# BalanceTest.net
KiCad netlist of a schematic drawn in EAGLE
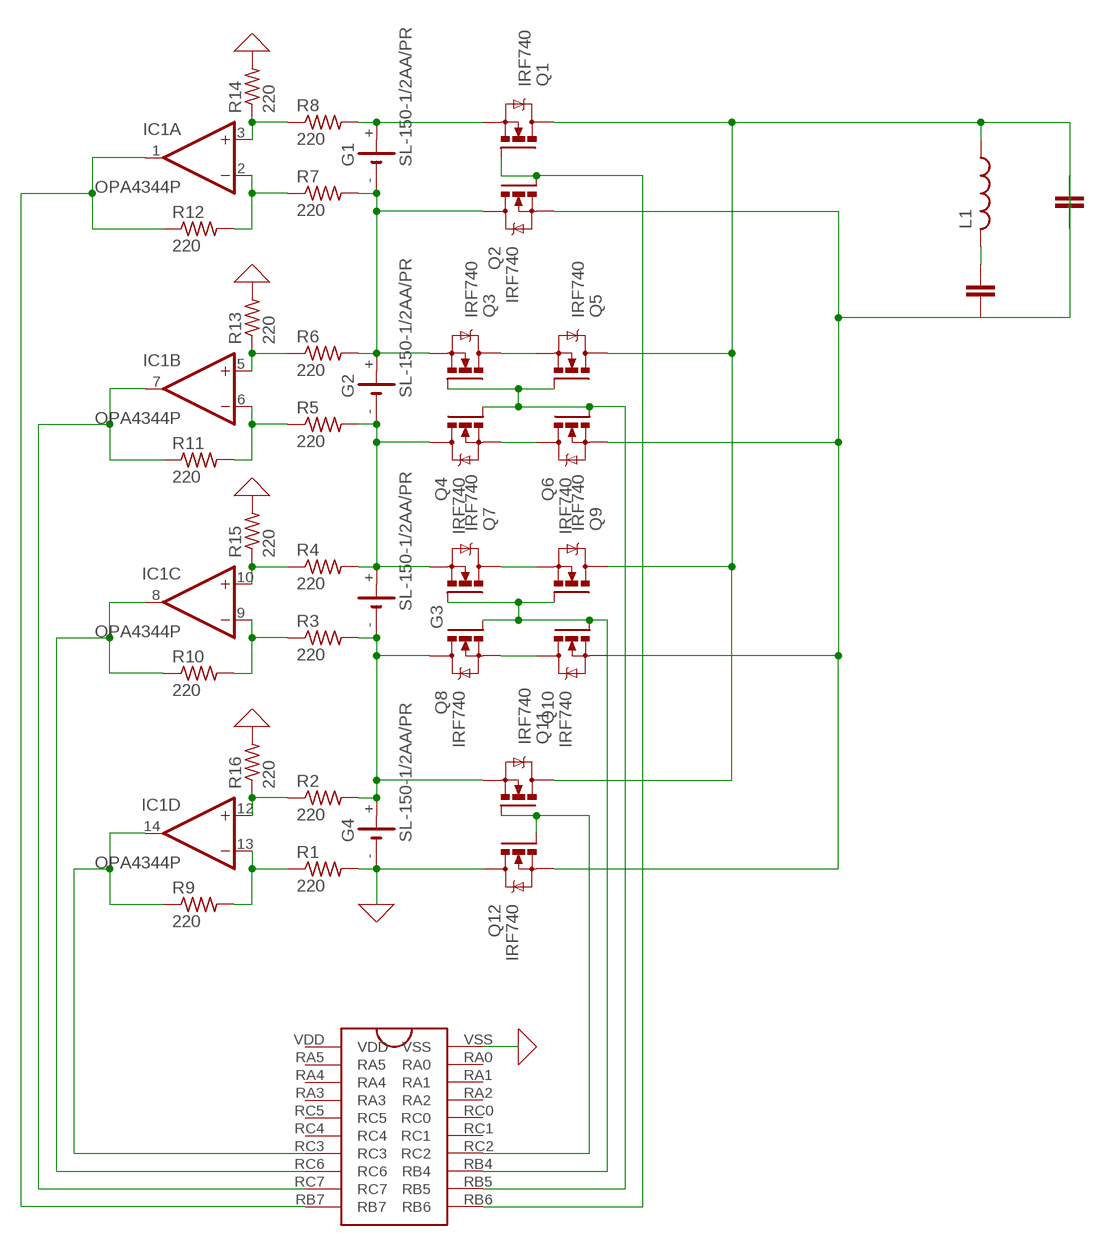
[diagram p0: schematic, sheet 1]

(export (version "E")
  (design (tool "Eeschema 10.0.6"))
  (components
    (comp (ref "G1")
      (value "SL-150-1/2AA/PR")
      (footprint "eagle-import:SL-150-1_2AA_PR")
      (libsource (lib "eagle-import") (part "SL-150-1/2AA/PR"))
    )
    (comp (ref "G2")
      (value "SL-150-1/2AA/PR")
      (footprint "eagle-import:SL-150-1_2AA_PR")
      (libsource (lib "eagle-import") (part "SL-150-1/2AA/PR"))
    )
    (comp (ref "G3")
      (value "SL-150-1/2AA/PR")
      (footprint "eagle-import:SL-150-1_2AA_PR")
      (libsource (lib "eagle-import") (part "SL-150-1/2AA/PR"))
    )
    (comp (ref "G4")
      (value "SL-150-1/2AA/PR")
      (footprint "eagle-import:SL-150-1_2AA_PR")
      (libsource (lib "eagle-import") (part "SL-150-1/2AA/PR"))
    )
    (comp (ref "IC1")
      (value "OPA4344P")
      (footprint "eagle-import:DIL14")
      (libsource (lib "eagle-import") (part "OPA4P344"))
    )
    (comp (ref "L1")
      (value "L-USIR-4")
      (footprint "eagle-import:IR-4")
      (libsource (lib "eagle-import") (part "L-USIR-4"))
    )
    (comp (ref "Q1")
      (value "IRF740")
      (footprint "eagle-import:TO220BV")
      (libsource (lib "eagle-import") (part "IRF740"))
    )
    (comp (ref "Q2")
      (value "IRF740")
      (footprint "eagle-import:TO220BV")
      (libsource (lib "eagle-import") (part "IRF740"))
    )
    (comp (ref "Q3")
      (value "IRF740")
      (footprint "eagle-import:TO220BV")
      (libsource (lib "eagle-import") (part "IRF740"))
    )
    (comp (ref "Q4")
      (value "IRF740")
      (footprint "eagle-import:TO220BV")
      (libsource (lib "eagle-import") (part "IRF740"))
    )
    (comp (ref "Q5")
      (value "IRF740")
      (footprint "eagle-import:TO220BV")
      (libsource (lib "eagle-import") (part "IRF740"))
    )
    (comp (ref "Q6")
      (value "IRF740")
      (footprint "eagle-import:TO220BV")
      (libsource (lib "eagle-import") (part "IRF740"))
    )
    (comp (ref "Q7")
      (value "IRF740")
      (footprint "eagle-import:TO220BV")
      (libsource (lib "eagle-import") (part "IRF740"))
    )
    (comp (ref "Q8")
      (value "IRF740")
      (footprint "eagle-import:TO220BV")
      (libsource (lib "eagle-import") (part "IRF740"))
    )
    (comp (ref "Q9")
      (value "IRF740")
      (footprint "eagle-import:TO220BV")
      (libsource (lib "eagle-import") (part "IRF740"))
    )
    (comp (ref "Q10")
      (value "IRF740")
      (footprint "eagle-import:TO220BV")
      (libsource (lib "eagle-import") (part "IRF740"))
    )
    (comp (ref "Q11")
      (value "IRF740")
      (footprint "eagle-import:TO220BV")
      (libsource (lib "eagle-import") (part "IRF740"))
    )
    (comp (ref "Q12")
      (value "IRF740")
      (footprint "eagle-import:TO220BV")
      (libsource (lib "eagle-import") (part "IRF740"))
    )
    (comp (ref "R1")
      (value "220")
      (footprint "eagle-import:0411_15")
      (libsource (lib "eagle-import") (part "R-US_0411/15"))
    )
    (comp (ref "R2")
      (value "220")
      (footprint "eagle-import:0411_15")
      (libsource (lib "eagle-import") (part "R-US_0411/15"))
    )
    (comp (ref "R3")
      (value "220")
      (footprint "eagle-import:0411_15")
      (libsource (lib "eagle-import") (part "R-US_0411/15"))
    )
    (comp (ref "R4")
      (value "220")
      (footprint "eagle-import:0411_15")
      (libsource (lib "eagle-import") (part "R-US_0411/15"))
    )
    (comp (ref "R5")
      (value "220")
      (footprint "eagle-import:0411_15")
      (libsource (lib "eagle-import") (part "R-US_0411/15"))
    )
    (comp (ref "R6")
      (value "220")
      (footprint "eagle-import:0411_15")
      (libsource (lib "eagle-import") (part "R-US_0411/15"))
    )
    (comp (ref "R7")
      (value "220")
      (footprint "eagle-import:0411_15")
      (libsource (lib "eagle-import") (part "R-US_0411/15"))
    )
    (comp (ref "R8")
      (value "220")
      (footprint "eagle-import:0411_15")
      (libsource (lib "eagle-import") (part "R-US_0411/15"))
    )
    (comp (ref "R9")
      (value "220")
      (footprint "eagle-import:0411_15")
      (libsource (lib "eagle-import") (part "R-US_0411/15"))
    )
    (comp (ref "R10")
      (value "220")
      (footprint "eagle-import:0411_15")
      (libsource (lib "eagle-import") (part "R-US_0411/15"))
    )
    (comp (ref "R11")
      (value "220")
      (footprint "eagle-import:0411_15")
      (libsource (lib "eagle-import") (part "R-US_0411/15"))
    )
    (comp (ref "R12")
      (value "220")
      (footprint "eagle-import:0411_15")
      (libsource (lib "eagle-import") (part "R-US_0411/15"))
    )
    (comp (ref "R13")
      (value "220")
      (footprint "eagle-import:0411_15")
      (libsource (lib "eagle-import") (part "R-US_0411/15"))
    )
    (comp (ref "R14")
      (value "220")
      (footprint "eagle-import:0411_15")
      (libsource (lib "eagle-import") (part "R-US_0411/15"))
    )
    (comp (ref "R15")
      (value "220")
      (footprint "eagle-import:0411_15")
      (libsource (lib "eagle-import") (part "R-US_0411/15"))
    )
    (comp (ref "R16")
      (value "220")
      (footprint "eagle-import:0411_15")
      (libsource (lib "eagle-import") (part "R-US_0411/15"))
    )
    (comp (ref "U1")
      (value "PIC18F15Q40SOIC")
      (footprint "eagle-import:SOIC")
      (libsource (lib "eagle-import") (part "PIC18F15Q40SOIC"))
    )
  )
  (nets
    (net (code "1") (name "GND") (class "Default")
      (node (ref "G4") (pin "-") (pinfunction "-_-") (pintype "passive"))
      (node (ref "Q12") (pin "D") (pinfunction "D_D") (pintype "passive"))
      (node (ref "R1") (pin "2") (pinfunction "2_2") (pintype "passive"))
      (node (ref "R13") (pin "2") (pinfunction "2_2") (pintype "passive"))
      (node (ref "R14") (pin "2") (pinfunction "2_2") (pintype "passive"))
      (node (ref "R15") (pin "2") (pinfunction "2_2") (pintype "passive"))
      (node (ref "R16") (pin "2") (pinfunction "2_2") (pintype "passive"))
      (node (ref "U1") (pin "VSS") (pinfunction "VSS_VSS") (pintype "bidirectional"))
    )
    (net (code "2") (name "Net-(G1-Pad+)") (class "Default")
      (node (ref "G1") (pin "+") (pinfunction "+_+") (pintype "passive"))
      (node (ref "Q1") (pin "S") (pinfunction "S_S") (pintype "passive"))
      (node (ref "R8") (pin "2") (pinfunction "2_2") (pintype "passive"))
    )
    (net (code "3") (name "Net-(G1-Pad-)") (class "Default")
      (node (ref "G1") (pin "-") (pinfunction "-_-") (pintype "passive"))
      (node (ref "G2") (pin "+") (pinfunction "+_+") (pintype "passive"))
      (node (ref "Q2") (pin "D") (pinfunction "D_D") (pintype "passive"))
      (node (ref "Q3") (pin "S") (pinfunction "S_S") (pintype "passive"))
      (node (ref "R6") (pin "2") (pinfunction "2_2") (pintype "passive"))
      (node (ref "R7") (pin "2") (pinfunction "2_2") (pintype "passive"))
    )
    (net (code "4") (name "Net-(G2-Pad-)") (class "Default")
      (node (ref "G2") (pin "-") (pinfunction "-_-") (pintype "passive"))
      (node (ref "G3") (pin "+") (pinfunction "+_+") (pintype "passive"))
      (node (ref "Q4") (pin "D") (pinfunction "D_D") (pintype "passive"))
      (node (ref "Q7") (pin "S") (pinfunction "S_S") (pintype "passive"))
      (node (ref "R4") (pin "2") (pinfunction "2_2") (pintype "passive"))
      (node (ref "R5") (pin "2") (pinfunction "2_2") (pintype "passive"))
    )
    (net (code "5") (name "Net-(G3-Pad-)") (class "Default")
      (node (ref "G3") (pin "-") (pinfunction "-_-") (pintype "passive"))
      (node (ref "G4") (pin "+") (pinfunction "+_+") (pintype "passive"))
      (node (ref "Q11") (pin "S") (pinfunction "S_S") (pintype "passive"))
      (node (ref "Q8") (pin "D") (pinfunction "D_D") (pintype "passive"))
      (node (ref "R2") (pin "2") (pinfunction "2_2") (pintype "passive"))
      (node (ref "R3") (pin "2") (pinfunction "2_2") (pintype "passive"))
    )
    (net (code "6") (name "Net-(IC1A-+IN)") (class "Default")
      (node (ref "IC1") (pin "3") (pinfunction "+IN_3") (pintype "input"))
      (node (ref "R14") (pin "1") (pinfunction "1_1") (pintype "passive"))
      (node (ref "R8") (pin "1") (pinfunction "1_1") (pintype "passive"))
    )
    (net (code "7") (name "Net-(IC1A--IN)") (class "Default")
      (node (ref "IC1") (pin "2") (pinfunction "-IN_2") (pintype "input"))
      (node (ref "R12") (pin "2") (pinfunction "2_2") (pintype "passive"))
      (node (ref "R7") (pin "1") (pinfunction "1_1") (pintype "passive"))
    )
    (net (code "8") (name "Net-(IC1A-OUT)") (class "Default")
      (node (ref "IC1") (pin "1") (pinfunction "OUT_1") (pintype "output"))
      (node (ref "R12") (pin "1") (pinfunction "1_1") (pintype "passive"))
      (node (ref "U1") (pin "RB7") (pinfunction "RB7_RB7") (pintype "bidirectional"))
    )
    (net (code "9") (name "Net-(IC1B-+IN)") (class "Default")
      (node (ref "IC1") (pin "5") (pinfunction "+IN_5") (pintype "input"))
      (node (ref "R13") (pin "1") (pinfunction "1_1") (pintype "passive"))
      (node (ref "R6") (pin "1") (pinfunction "1_1") (pintype "passive"))
    )
    (net (code "10") (name "Net-(IC1B--IN)") (class "Default")
      (node (ref "IC1") (pin "6") (pinfunction "-IN_6") (pintype "input"))
      (node (ref "R11") (pin "2") (pinfunction "2_2") (pintype "passive"))
      (node (ref "R5") (pin "1") (pinfunction "1_1") (pintype "passive"))
    )
    (net (code "11") (name "Net-(IC1B-OUT)") (class "Default")
      (node (ref "IC1") (pin "7") (pinfunction "OUT_7") (pintype "output"))
      (node (ref "R11") (pin "1") (pinfunction "1_1") (pintype "passive"))
      (node (ref "U1") (pin "RC7") (pinfunction "RC7_RC7") (pintype "bidirectional"))
    )
    (net (code "12") (name "Net-(IC1C-+IN)") (class "Default")
      (node (ref "IC1") (pin "10") (pinfunction "+IN_10") (pintype "input"))
      (node (ref "R15") (pin "1") (pinfunction "1_1") (pintype "passive"))
      (node (ref "R4") (pin "1") (pinfunction "1_1") (pintype "passive"))
    )
    (net (code "13") (name "Net-(IC1C--IN)") (class "Default")
      (node (ref "IC1") (pin "9") (pinfunction "-IN_9") (pintype "input"))
      (node (ref "R10") (pin "2") (pinfunction "2_2") (pintype "passive"))
      (node (ref "R3") (pin "1") (pinfunction "1_1") (pintype "passive"))
    )
    (net (code "14") (name "Net-(IC1C-OUT)") (class "Default")
      (node (ref "IC1") (pin "8") (pinfunction "OUT_8") (pintype "output"))
      (node (ref "R10") (pin "1") (pinfunction "1_1") (pintype "passive"))
      (node (ref "U1") (pin "RC6") (pinfunction "RC6_RC6") (pintype "bidirectional"))
    )
    (net (code "15") (name "Net-(IC1D-+IN)") (class "Default")
      (node (ref "IC1") (pin "12") (pinfunction "+IN_12") (pintype "input"))
      (node (ref "R16") (pin "1") (pinfunction "1_1") (pintype "passive"))
      (node (ref "R2") (pin "1") (pinfunction "1_1") (pintype "passive"))
    )
    (net (code "16") (name "Net-(IC1D--IN)") (class "Default")
      (node (ref "IC1") (pin "13") (pinfunction "-IN_13") (pintype "input"))
      (node (ref "R1") (pin "1") (pinfunction "1_1") (pintype "passive"))
      (node (ref "R9") (pin "2") (pinfunction "2_2") (pintype "passive"))
    )
    (net (code "17") (name "Net-(IC1D-OUT)") (class "Default")
      (node (ref "IC1") (pin "14") (pinfunction "OUT_14") (pintype "output"))
      (node (ref "R9") (pin "1") (pinfunction "1_1") (pintype "passive"))
      (node (ref "U1") (pin "RC3") (pinfunction "RC3_RC3") (pintype "bidirectional"))
    )
    (net (code "18") (name "Net-(L1-Pad1)") (class "Default")
      (node (ref "L1") (pin "1") (pinfunction "1_1") (pintype "passive"))
      (node (ref "Q1") (pin "D") (pinfunction "D_D") (pintype "passive"))
      (node (ref "Q10") (pin "S") (pinfunction "S_S") (pintype "passive"))
      (node (ref "Q11") (pin "D") (pinfunction "D_D") (pintype "passive"))
      (node (ref "Q12") (pin "S") (pinfunction "S_S") (pintype "passive"))
      (node (ref "Q2") (pin "S") (pinfunction "S_S") (pintype "passive"))
      (node (ref "Q5") (pin "D") (pinfunction "D_D") (pintype "passive"))
      (node (ref "Q6") (pin "S") (pinfunction "S_S") (pintype "passive"))
      (node (ref "Q9") (pin "D") (pinfunction "D_D") (pintype "passive"))
    )
    (net (code "19") (name "Net-(Q1-PadG)") (class "Default")
      (node (ref "Q1") (pin "G") (pinfunction "G_G") (pintype "passive"))
      (node (ref "Q2") (pin "G") (pinfunction "G_G") (pintype "passive"))
      (node (ref "U1") (pin "RB6") (pinfunction "RB6_RB6") (pintype "bidirectional"))
    )
    (net (code "20") (name "Net-(Q3-PadD)") (class "Default")
      (node (ref "Q3") (pin "D") (pinfunction "D_D") (pintype "passive"))
      (node (ref "Q5") (pin "S") (pinfunction "S_S") (pintype "passive"))
    )
    (net (code "21") (name "Net-(Q3-PadG)") (class "Default")
      (node (ref "Q3") (pin "G") (pinfunction "G_G") (pintype "passive"))
      (node (ref "Q4") (pin "G") (pinfunction "G_G") (pintype "passive"))
      (node (ref "Q5") (pin "G") (pinfunction "G_G") (pintype "passive"))
      (node (ref "Q6") (pin "G") (pinfunction "G_G") (pintype "passive"))
      (node (ref "U1") (pin "RB5") (pinfunction "RB5_RB5") (pintype "bidirectional"))
    )
    (net (code "22") (name "Net-(Q4-PadS)") (class "Default")
      (node (ref "Q4") (pin "S") (pinfunction "S_S") (pintype "passive"))
      (node (ref "Q6") (pin "D") (pinfunction "D_D") (pintype "passive"))
    )
    (net (code "23") (name "Net-(Q7-PadD)") (class "Default")
      (node (ref "Q7") (pin "D") (pinfunction "D_D") (pintype "passive"))
      (node (ref "Q9") (pin "S") (pinfunction "S_S") (pintype "passive"))
    )
    (net (code "24") (name "Net-(Q10-PadD)") (class "Default")
      (node (ref "Q10") (pin "D") (pinfunction "D_D") (pintype "passive"))
      (node (ref "Q8") (pin "S") (pinfunction "S_S") (pintype "passive"))
    )
    (net (code "25") (name "Net-(Q10-PadG)") (class "Default")
      (node (ref "Q10") (pin "G") (pinfunction "G_G") (pintype "passive"))
      (node (ref "Q7") (pin "G") (pinfunction "G_G") (pintype "passive"))
      (node (ref "Q8") (pin "G") (pinfunction "G_G") (pintype "passive"))
      (node (ref "Q9") (pin "G") (pinfunction "G_G") (pintype "passive"))
      (node (ref "U1") (pin "RB4") (pinfunction "RB4_RB4") (pintype "bidirectional"))
    )
    (net (code "26") (name "Net-(Q11-PadG)") (class "Default")
      (node (ref "Q11") (pin "G") (pinfunction "G_G") (pintype "passive"))
      (node (ref "Q12") (pin "G") (pinfunction "G_G") (pintype "passive"))
      (node (ref "U1") (pin "RC2") (pinfunction "RC2_RC2") (pintype "bidirectional"))
    )
    (net (code "27") (name "unconnected-(L1-Pad2)") (class "Default")
      (node (ref "L1") (pin "2") (pinfunction "2_2") (pintype "passive"))
    )
    (net (code "28") (name "unconnected-(U1-PadRA0)") (class "Default")
      (node (ref "U1") (pin "RA0") (pinfunction "RA0_RA0") (pintype "bidirectional"))
    )
    (net (code "29") (name "unconnected-(U1-PadRA1)") (class "Default")
      (node (ref "U1") (pin "RA1") (pinfunction "RA1_RA1") (pintype "bidirectional"))
    )
    (net (code "30") (name "unconnected-(U1-PadRA2)") (class "Default")
      (node (ref "U1") (pin "RA2") (pinfunction "RA2_RA2") (pintype "bidirectional"))
    )
    (net (code "31") (name "unconnected-(U1-PadRA3)") (class "Default")
      (node (ref "U1") (pin "RA3") (pinfunction "RA3_RA3") (pintype "bidirectional"))
    )
    (net (code "32") (name "unconnected-(U1-PadRA4)") (class "Default")
      (node (ref "U1") (pin "RA4") (pinfunction "RA4_RA4") (pintype "bidirectional"))
    )
    (net (code "33") (name "unconnected-(U1-PadRA5)") (class "Default")
      (node (ref "U1") (pin "RA5") (pinfunction "RA5_RA5") (pintype "bidirectional"))
    )
    (net (code "34") (name "unconnected-(U1-PadRC0)") (class "Default")
      (node (ref "U1") (pin "RC0") (pinfunction "RC0_RC0") (pintype "bidirectional"))
    )
    (net (code "35") (name "unconnected-(U1-PadRC1)") (class "Default")
      (node (ref "U1") (pin "RC1") (pinfunction "RC1_RC1") (pintype "bidirectional"))
    )
    (net (code "36") (name "unconnected-(U1-PadRC4)") (class "Default")
      (node (ref "U1") (pin "RC4") (pinfunction "RC4_RC4") (pintype "bidirectional"))
    )
    (net (code "37") (name "unconnected-(U1-PadRC5)") (class "Default")
      (node (ref "U1") (pin "RC5") (pinfunction "RC5_RC5") (pintype "bidirectional"))
    )
    (net (code "38") (name "unconnected-(U1-PadVDD)") (class "Default")
      (node (ref "U1") (pin "VDD") (pinfunction "VDD_VDD") (pintype "bidirectional"))
    )
  )
)
